# Regulator_3v3-250mA_MCP1702.net
KiCad netlist of a schematic drawn in Altium Designer
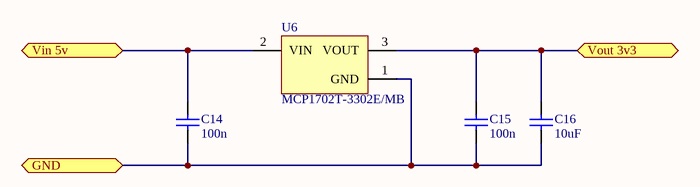
[diagram p0: Regulator 3v3-250mA MCP1702.SchDoc]

(export (version "E")
  (design (tool "Eeschema 10.0.6"))
  (components
    (comp (ref "C14")
      (value "100n")
      (footprint "C0805")
      (fields (field (name "TOLERANCE") "0.1") (field (name "AUTHOR") "Willy Pietersz"))
      (libsource (lib "OurDb") (part "cap_NonPolar"))
    )
    (comp (ref "C15")
      (value "100n")
      (footprint "C0805")
      (fields (field (name "TOLERANCE") "0.1") (field (name "AUTHOR") "Willy Pietersz"))
      (libsource (lib "OurDb") (part "cap_NonPolar"))
    )
    (comp (ref "C16")
      (value "10uF")
      (footprint "C1206")
      (fields
        (field (name "VOLTAGE") "10V")
        (field (name "TOLERANCE") "0.1")
        (field (name "AUTHOR") "Willem Pietersz")
      )
      (libsource (lib "OurDb") (part "cap_NonPolar"))
    )
    (comp (ref "U6")
      (value "MCP1702T-3302E/MB")
      (footprint "SOT-89-MB3_N")
      (fields (field (name "PUBLISHER") "Altium Limited"))
      (libsource (lib "AltiumDatabaseSelection") (part "MCP1702T-3302E/MB"))
    )
  )
  (nets
    (net (code "1") (name "/GND") (class "Default")
      (node (ref "C14") (pin "1") (pinfunction "1_1") (pintype "passive"))
      (node (ref "C15") (pin "1") (pinfunction "1_1") (pintype "passive"))
      (node (ref "C16") (pin "1") (pinfunction "1_1") (pintype "passive"))
      (node (ref "U6") (pin "1") (pinfunction "GND_1") (pintype "power_in"))
    )
    (net (code "2") (name "/Vin 5v") (class "Default")
      (node (ref "C14") (pin "2") (pinfunction "2_2") (pintype "passive"))
      (node (ref "U6") (pin "2") (pinfunction "VIN_2") (pintype "power_in"))
    )
    (net (code "3") (name "/Vout 3v3") (class "Default")
      (node (ref "C15") (pin "2") (pinfunction "2_2") (pintype "passive"))
      (node (ref "C16") (pin "2") (pinfunction "2_2") (pintype "passive"))
      (node (ref "U6") (pin "3") (pinfunction "VOUT_3") (pintype "power_in"))
    )
  )
)
